# 2.net
KiCad netlist of a schematic drawn in Altium Designer
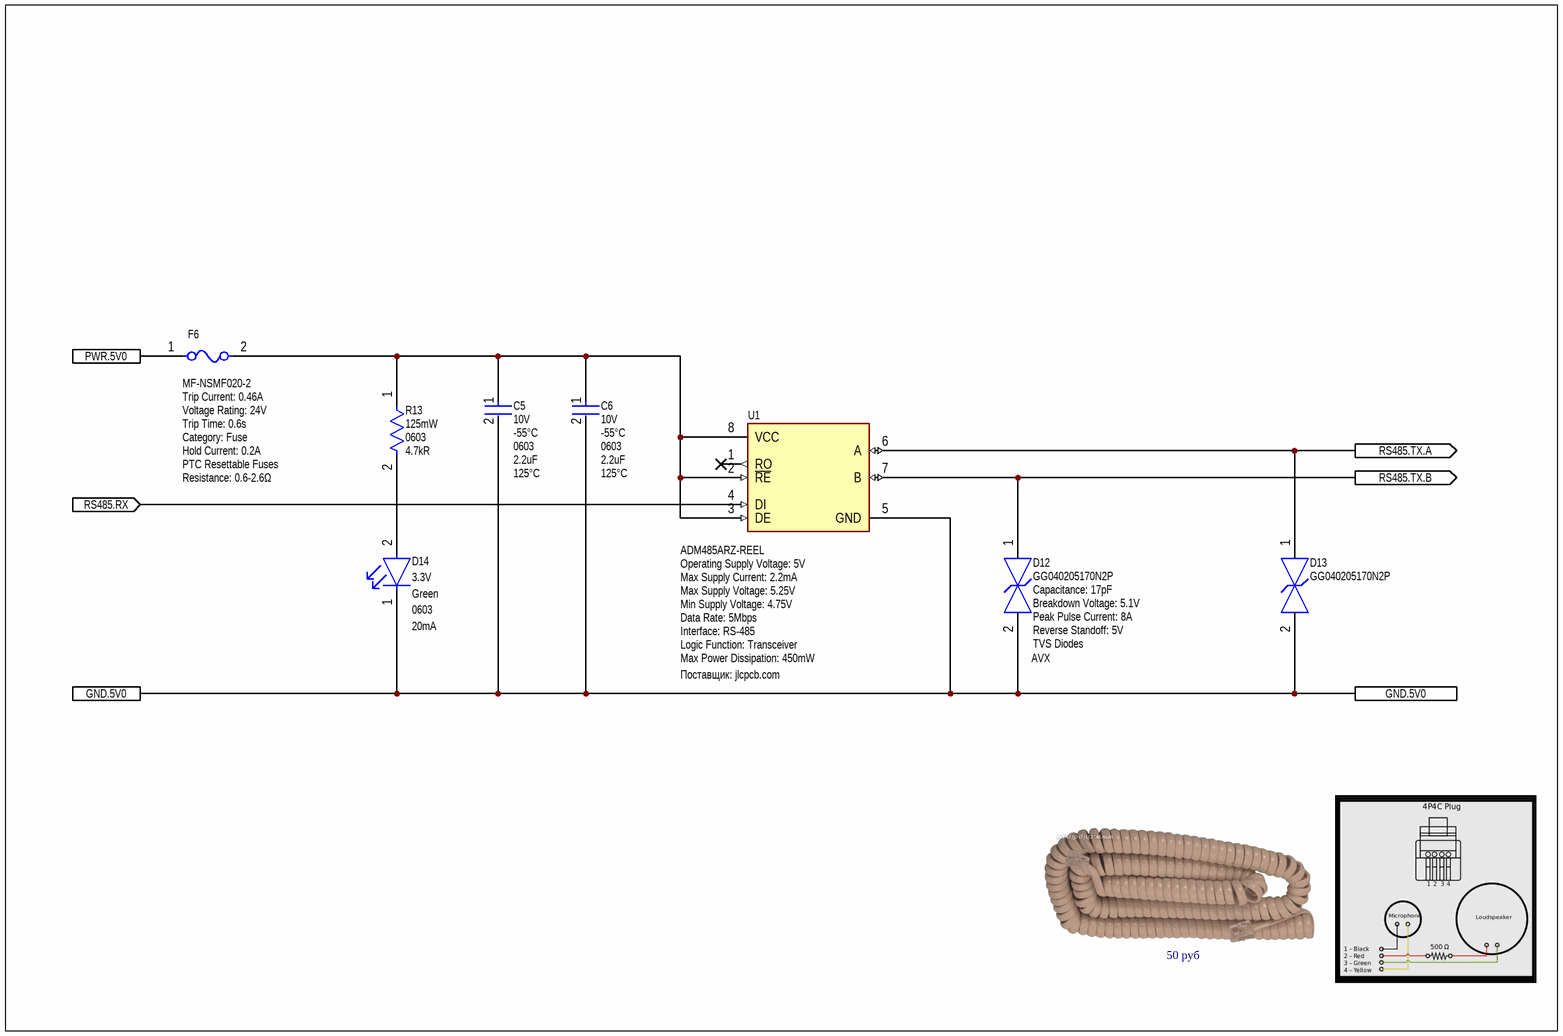
[diagram p0: Блок2.SchDoc]

(export (version "E")
  (design (tool "Eeschema 10.0.6"))
  (components
    (comp (ref "C5")
      (value "CL10B225KP8NFNC")
      (footprint "FP-CL10-IPC_A")
      (description "Cap Ceramic 2.2uF 10V X7R ±10% Pad SMD 0603 +125°C T/R")
      (fields
        (field (name "VOLTAGE RATING") "10V")
        (field (name "MIN OPERATING TEMPERATURE") "-55°C")
        (field (name "CASE CODE (IMPERIAL)") "0603")
        (field (name "CAPACITANCE") "2.2uF")
        (field (name "MAX OPERATING TEMPERATURE") "125°C")
        (field (name "TOLERANCE") "10%")
      )
      (libsource (lib "Altium Content Vault") (part "b4654b650e69147ec39a6b967a45e02"))
    )
    (comp (ref "C6")
      (value "CL10B225KP8NFNC")
      (footprint "FP-CL10-IPC_A")
      (description "Cap Ceramic 2.2uF 10V X7R ±10% Pad SMD 0603 +125°C T/R")
      (fields
        (field (name "VOLTAGE RATING") "10V")
        (field (name "MIN OPERATING TEMPERATURE") "-55°C")
        (field (name "CASE CODE (IMPERIAL)") "0603")
        (field (name "CAPACITANCE") "2.2uF")
        (field (name "MAX OPERATING TEMPERATURE") "125°C")
        (field (name "TOLERANCE") "10%")
      )
      (libsource (lib "Altium Content Vault") (part "b4654b650e69147ec39a6b967a45e02"))
    )
    (comp (ref "D12")
      (value "GG040205170N2P")
      (footprint "FP-GG0402-IPC_A")
      (description "TVS DIODE 5V 10V 0402")
      (fields
        (field (name "OCTOPART") "https://octopart.com/gg040205170n2p-avx-81066082")
        (field (name "CAPACITANCE") "17pF")
        (field (name "MANUFACTURER") "AVX")
        (field (name "BREAKDOWN VOLTAGE") "5.1V")
        (field (name "PEAK PULSE CURRENT") "8A")
        (field (name "REVERSE STANDOFF") "5V")
        (field (name "DEVICE CLASS L2") "TVS Diodes")
      )
      (libsource (lib "Altium Content Vault") (part "11bd9d59d340f0612179daf16ad9b72"))
    )
    (comp (ref "D13")
      (value "GG040205170N2P")
      (footprint "FP-GG0402-IPC_A")
      (description "TVS DIODE 5V 10V 0402")
      (fields
        (field (name "OCTOPART") "https://octopart.com/gg040205170n2p-avx-81066082")
        (field (name "MANUFACTURER") "AVX")
      )
      (libsource (lib "Altium Content Vault") (part "11bd9d59d340f0612179daf16ad9b72"))
    )
    (comp (ref "D14")
      (value "APT1608ZGCK")
      (footprint "FP-APT1608ZGCK-MFG")
      (description "LED GREEN CLEAR CHIP SMD")
      (fields
        (field (name "FORWARD VOLTAGE") "3.3V")
        (field (name "COLOR") "Green")
        (field (name "CASE/PACKAGE") "0603")
        (field (name "FORWARD CURRENT") "20mA")
      )
      (libsource (lib "Altium Content Vault") (part "8706943c75ba83719d021d2fdc84c58"))
    )
    (comp (ref "F6")
      (value "MF-NSMF020-2")
      (footprint "FP-MF-NSMF020-2-MFG")
      (description "PTC RESET FUSE 24V 200MA 1206")
      (fields
        (field (name "TRIP CURRENT") "0.46A")
        (field (name "VOLTAGE RATING") "24V")
        (field (name "TRIP TIME") "0.6s")
        (field (name "CATEGORY") "Fuse")
        (field (name "HOLD CURRENT") "0.2A")
        (field (name "DEVICE CLASS L2") "PTC Resettable Fuses")
        (field (name "MANUFACTURER") "Bourns")
        (field (name "OCTOPART") "https://octopart.com/mf-nsmf020-2-bourns-94649")
        (field (name "RESISTANCE") "0.6-2.6Ω")
      )
      (libsource (lib "Altium Content Vault") (part "5bcf9b9f640e542cf0359d10258e979"))
    )
    (comp (ref "R13")
      (value "MCT06030C4701FP500")
      (footprint "FP-MCT0603-MFG")
      (description "RES SMD 100 OHM 1% 1/8W 0603")
      (fields
        (field (name "POWER RATING") "125mW")
        (field (name "CASE/PACKAGE") "0603")
        (field (name "RESISTANCE") "4.7kR")
        (field (name "TOLERANCE") "1%")
      )
      (libsource (lib "Altium Content Vault") (part "1029c3af85768c4190bb7ad29bc67b5"))
    )
    (comp (ref "U1")
      (value "ADM485ARZ-REEL")
      (footprint "FP-R-8-IPC_C")
      (description "IC TRANSCEIVER HALF 1/1 8SOIC")
      (fields
        (field (name "MAX POWER DISSIPATION") "450mW")
        (field (name "MAX SUPPLY CURRENT") "2.2mA")
        (field (name "MAX SUPPLY VOLTAGE") "5.25V")
        (field (name "MIN SUPPLY VOLTAGE") "4.75V")
        (field (name "LOGIC FUNCTION") "Transceiver")
        (field (name "OPERATING SUPPLY VOLTAGE") "5V")
        (field (name "DATA RATE") "5Mbps")
        (field (name "INTERFACE") "RS-485")
        (field (name "ПОСТАВЩИК") "jlcpcb.com")
      )
      (libsource (lib "Altium Content Vault") (part "fc4f0899c62869684301c146cea964a"))
    )
  )
  (nets
    (net (code "1") (name "/GND.5V0") (class "Default")
      (node (ref "C5") (pin "2") (pinfunction "2_2") (pintype "passive"))
      (node (ref "C6") (pin "2") (pinfunction "2_2") (pintype "passive"))
      (node (ref "D12") (pin "2") (pinfunction "2_2") (pintype "passive"))
      (node (ref "D13") (pin "2") (pinfunction "2_2") (pintype "passive"))
      (node (ref "D14") (pin "1") (pinfunction "C_1") (pintype "passive"))
      (node (ref "U1") (pin "5") (pinfunction "GND_5") (pintype "power_in"))
    )
    (net (code "2") (name "/PWR.5V0") (class "Default")
      (node (ref "F6") (pin "1") (pinfunction "1_1") (pintype "passive"))
    )
    (net (code "3") (name "/RS485.RX") (class "Default")
      (node (ref "U1") (pin "4") (pinfunction "DI_4") (pintype "input"))
    )
    (net (code "4") (name "/RS485.TX.A") (class "Default")
      (node (ref "D13") (pin "1") (pinfunction "1_1") (pintype "passive"))
      (node (ref "U1") (pin "6") (pinfunction "A_6") (pintype "bidirectional"))
    )
    (net (code "5") (name "/RS485.TX.B") (class "Default")
      (node (ref "D12") (pin "1") (pinfunction "1_1") (pintype "passive"))
      (node (ref "U1") (pin "7") (pinfunction "B_7") (pintype "bidirectional"))
    )
    (net (code "6") (name "Net-(D14-A)") (class "Default")
      (node (ref "D14") (pin "2") (pinfunction "A_2") (pintype "passive"))
      (node (ref "R13") (pin "2") (pinfunction "2_2") (pintype "passive"))
    )
    (net (code "7") (name "Net-(U1-DE)") (class "Default")
      (node (ref "C5") (pin "1") (pinfunction "1_1") (pintype "passive"))
      (node (ref "C6") (pin "1") (pinfunction "1_1") (pintype "passive"))
      (node (ref "F6") (pin "2") (pinfunction "2_2") (pintype "passive"))
      (node (ref "R13") (pin "1") (pinfunction "1_1") (pintype "passive"))
      (node (ref "U1") (pin "2") (pinfunction "~{RE}_2") (pintype "input"))
      (node (ref "U1") (pin "3") (pinfunction "DE_3") (pintype "input"))
      (node (ref "U1") (pin "8") (pinfunction "VCC_8") (pintype "power_in"))
    )
    (net (code "8") (name "unconnected-(U1-RO-Pad1)") (class "Default")
      (node (ref "U1") (pin "1") (pinfunction "RO_1") (pintype "output+no_connect"))
    )
  )
)
